# dawa_v2_1.net
KiCad netlist of a schematic drawn in EAGLE
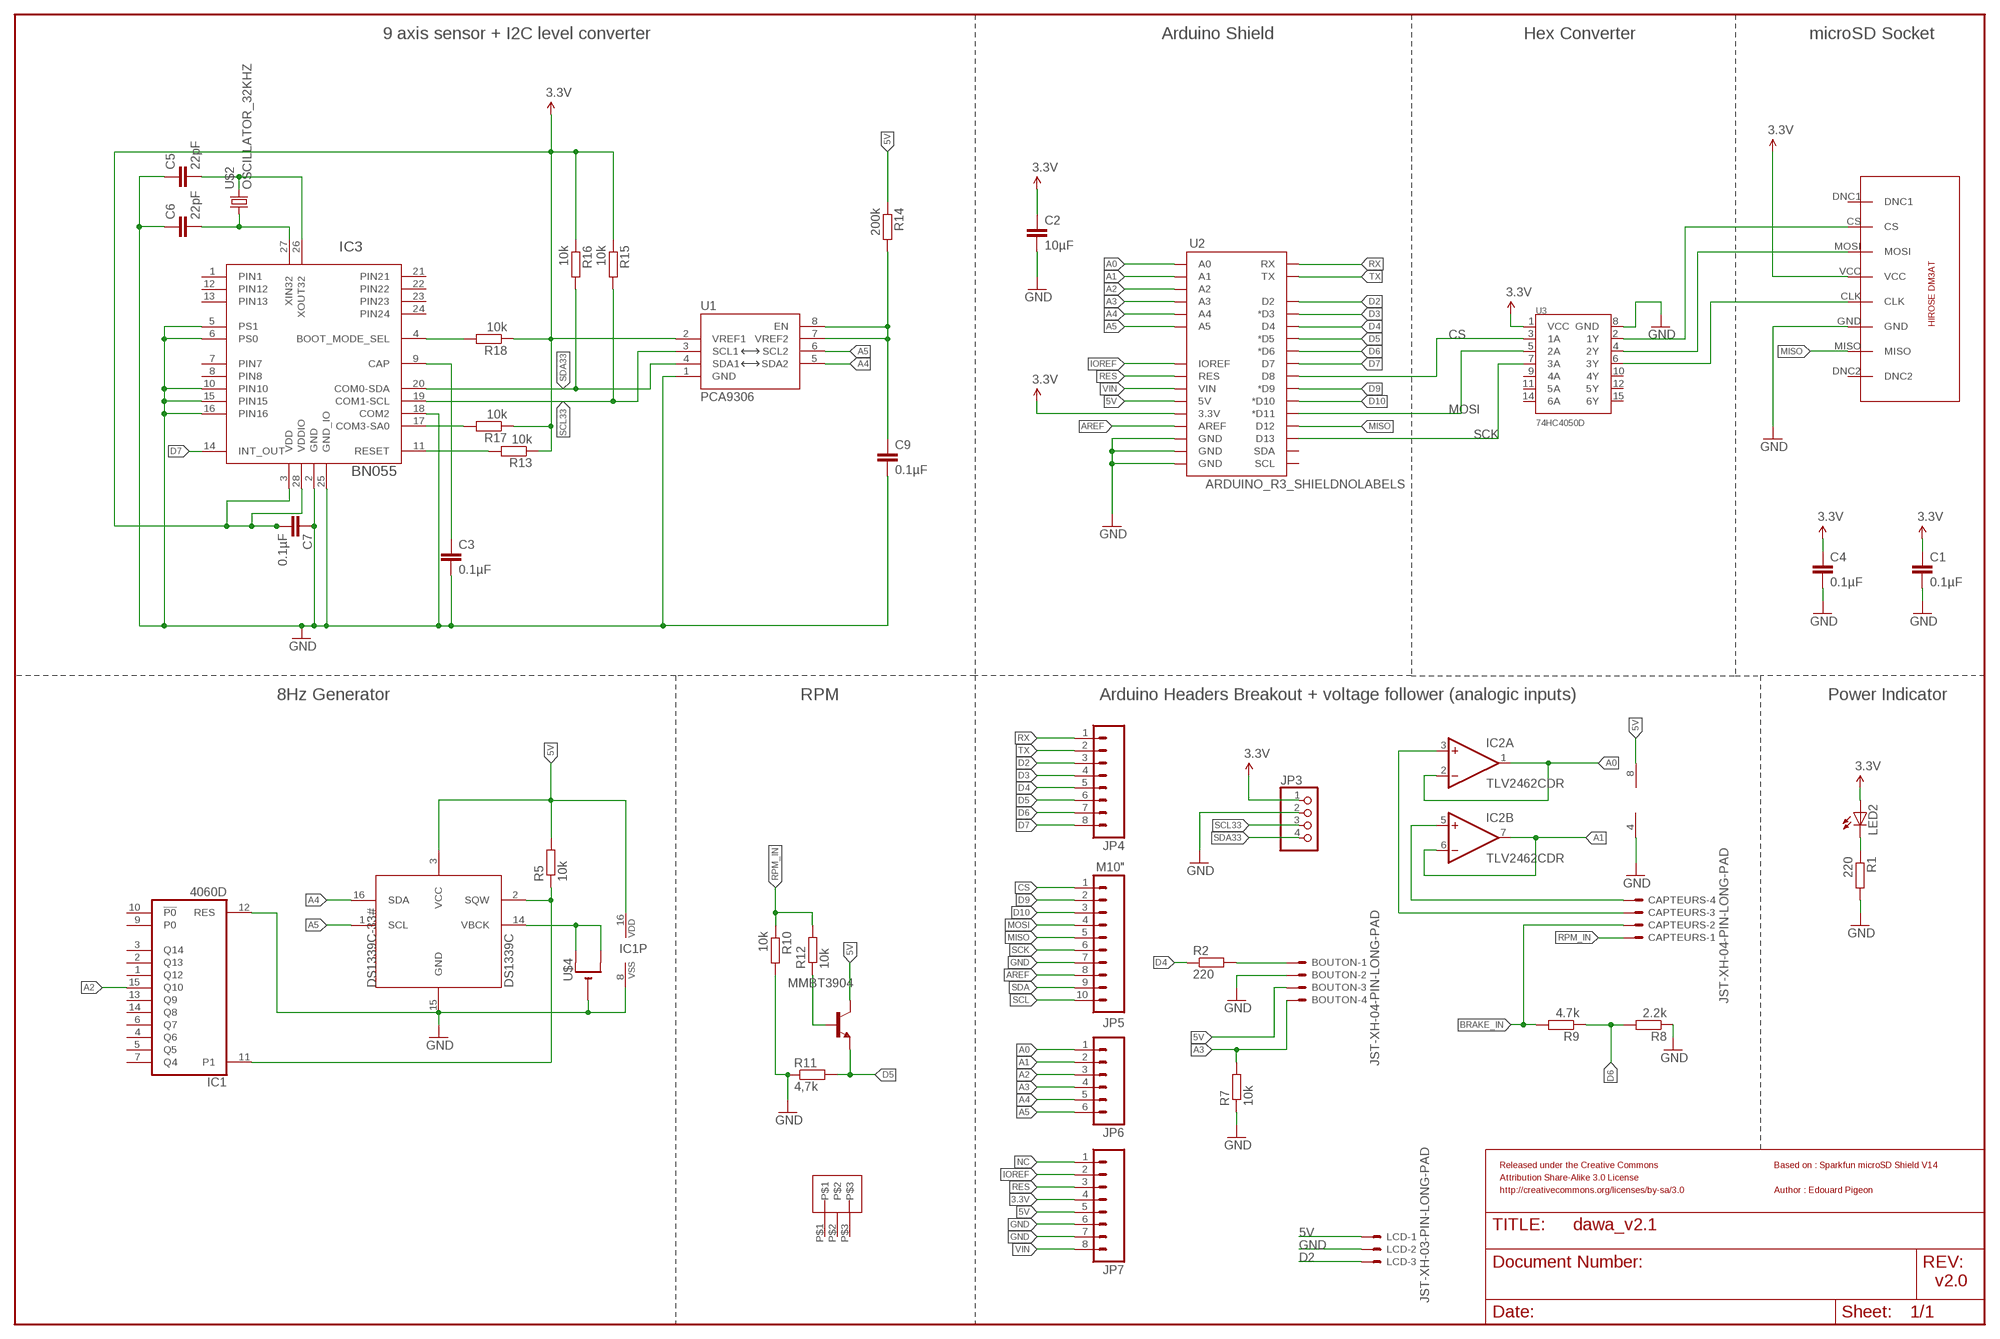
[diagram p0: schematic, sheet 1]

(export (version "E")
  (design (tool "Eeschema 10.0.6"))
  (components
    (comp (ref "BOUTON")
      (value "JST-XH-04-PIN-LONG-PAD")
      (footprint "eagle-import:JST-XH-04-PACKAGE-LONG-PAD")
      (libsource (lib "eagle-import") (part "JST-XH-04-PIN-LONG-PAD"))
    )
    (comp (ref "C1")
      (value "0.1µF")
      (footprint "eagle-import:C1206")
      (libsource (lib "eagle-import") (part "C-EUC1206"))
    )
    (comp (ref "C2")
      (value "10µF")
      (footprint "eagle-import:C1206")
      (libsource (lib "eagle-import") (part "C-EUC1206"))
    )
    (comp (ref "C3")
      (value "0.1µF")
      (footprint "eagle-import:C1206")
      (libsource (lib "eagle-import") (part "C-EUC1206"))
    )
    (comp (ref "C4")
      (value "0.1µF")
      (footprint "eagle-import:C1206")
      (libsource (lib "eagle-import") (part "C-EUC1206"))
    )
    (comp (ref "C5")
      (value "22pF")
      (footprint "eagle-import:C1206")
      (libsource (lib "eagle-import") (part "C-EUC1206"))
    )
    (comp (ref "C6")
      (value "22pF")
      (footprint "eagle-import:C1206")
      (libsource (lib "eagle-import") (part "C-EUC1206"))
    )
    (comp (ref "C7")
      (value "0.1µF")
      (footprint "eagle-import:C1206")
      (libsource (lib "eagle-import") (part "C-EUC1206"))
    )
    (comp (ref "C9")
      (value "0.1µF")
      (footprint "eagle-import:C1206")
      (libsource (lib "eagle-import") (part "C-EUC1206"))
    )
    (comp (ref "CAPTEURS")
      (value "JST-XH-04-PIN-LONG-PAD")
      (footprint "eagle-import:JST-XH-04-PACKAGE-LONG-PAD")
      (libsource (lib "eagle-import") (part "JST-XH-04-PIN-LONG-PAD"))
    )
    (comp (ref "DS1339C-33#")
      (value "DS1339C")
      (footprint "eagle-import:DS1339C")
      (libsource (lib "eagle-import") (part "DS1339C"))
    )
    (comp (ref "IC1")
      (value "4060D")
      (footprint "eagle-import:SO16")
      (libsource (lib "eagle-import") (part "4060D"))
    )
    (comp (ref "IC2")
      (value "TLV2462CDR")
      (footprint "eagle-import:SO08")
      (libsource (lib "eagle-import") (part "LM358MX"))
    )
    (comp (ref "IC3")
      (value "BN055")
      (footprint "eagle-import:LGA-28_3.80X5.20_0.5")
      (fields (field (name "PART_NUMBER") "BNO055"))
      (libsource (lib "eagle-import") (part "1658_BNO055"))
    )
    (comp (ref "JP3")
      (value "PINHD-1X4")
      (footprint "eagle-import:1X04")
      (libsource (lib "eagle-import") (part "PINHD-1X4"))
    )
    (comp (ref "JP4")
      (value "M08")
      (footprint "eagle-import:1X08")
      (libsource (lib "eagle-import") (part "M08"))
    )
    (comp (ref "JP5")
      (value "M10\"")
      (footprint "eagle-import:1X10")
      (libsource (lib "eagle-import") (part "M10{dblquote}"))
    )
    (comp (ref "JP6")
      (value "M06SIP")
      (footprint "eagle-import:1X06")
      (libsource (lib "eagle-import") (part "M06SIP"))
    )
    (comp (ref "JP7")
      (value "M081X08")
      (footprint "eagle-import:1X08")
      (libsource (lib "eagle-import") (part "M081X08"))
    )
    (comp (ref "LCD")
      (value "JST-XH-03-PIN-LONG-PAD")
      (footprint "eagle-import:JST-XH-03-PACKAGE-LONG-PAD")
      (libsource (lib "eagle-import") (part "JST-XH-03-PIN-LONG-PAD"))
    )
    (comp (ref "LED2")
      (value "LEDCHIPLED_1206")
      (footprint "eagle-import:CHIPLED_1206")
      (libsource (lib "eagle-import") (part "LEDCHIPLED_1206"))
    )
    (comp (ref "MMBT3904")
      (value "MMBT3904LT1-NPN-SOT23-BEC")
      (footprint "eagle-import:SOT23-BEC")
      (libsource (lib "eagle-import") (part "-NPN-SOT23-BECMMBT3904LT1"))
    )
    (comp (ref "R1")
      (value "220")
      (footprint "eagle-import:M1206")
      (libsource (lib "eagle-import") (part "resistor_R-EU_M1206"))
    )
    (comp (ref "R2")
      (value "220")
      (footprint "eagle-import:M1206")
      (libsource (lib "eagle-import") (part "resistor_R-EU_M1206"))
    )
    (comp (ref "R5")
      (value "10k")
      (footprint "eagle-import:M1206")
      (libsource (lib "eagle-import") (part "R-EU_M1206"))
    )
    (comp (ref "R7")
      (value "10k")
      (footprint "eagle-import:M1206")
      (libsource (lib "eagle-import") (part "resistor_R-EU_M1206"))
    )
    (comp (ref "R8")
      (value "2.2k")
      (footprint "eagle-import:M1206")
      (libsource (lib "eagle-import") (part "resistor_R-EU_M1206"))
    )
    (comp (ref "R9")
      (value "4.7k")
      (footprint "eagle-import:M1206")
      (libsource (lib "eagle-import") (part "resistor_R-EU_M1206"))
    )
    (comp (ref "R10")
      (value "10k")
      (footprint "eagle-import:M1206")
      (libsource (lib "eagle-import") (part "R-EU_M1206"))
    )
    (comp (ref "R11")
      (value "4,7k")
      (footprint "eagle-import:M1206")
      (libsource (lib "eagle-import") (part "R-EU_M1206"))
    )
    (comp (ref "R12")
      (value "10k")
      (footprint "eagle-import:M1206")
      (libsource (lib "eagle-import") (part "R-EU_M1206"))
    )
    (comp (ref "R13")
      (value "10k")
      (footprint "eagle-import:M1206")
      (libsource (lib "eagle-import") (part "R-EU_M1206"))
    )
    (comp (ref "R14")
      (value "200k")
      (footprint "eagle-import:M1206")
      (libsource (lib "eagle-import") (part "R-EU_M1206"))
    )
    (comp (ref "R15")
      (value "10k")
      (footprint "eagle-import:M1206")
      (libsource (lib "eagle-import") (part "R-EU_M1206"))
    )
    (comp (ref "R16")
      (value "10k")
      (footprint "eagle-import:M1206")
      (libsource (lib "eagle-import") (part "R-EU_M1206"))
    )
    (comp (ref "R17")
      (value "10k")
      (footprint "eagle-import:M1206")
      (libsource (lib "eagle-import") (part "R-EU_M1206"))
    )
    (comp (ref "R18")
      (value "10k")
      (footprint "eagle-import:M1206")
      (libsource (lib "eagle-import") (part "R-EU_M1206"))
    )
    (comp (ref "U$2")
      (value "OSCILLATOR_32KHZ")
      (footprint "eagle-import:OSCILLATOR_SMD")
      (libsource (lib "eagle-import") (part "OSCILLATOR_32KHZ"))
    )
    (comp (ref "U$3")
      (value "3_PIN_JST-XH")
      (footprint "eagle-import:3_PIN_JST-XH")
      (libsource (lib "eagle-import") (part "3_PIN_JST-XH"))
    )
    (comp (ref "U$4")
      (value "CR1220SMT")
      (footprint "eagle-import:CR1220-SMD")
      (libsource (lib "eagle-import") (part "CR1220SMT"))
    )
    (comp (ref "U$5")
      (value "DM3AT")
      (footprint "eagle-import:DM3AT")
      (libsource (lib "eagle-import") (part "DM3AT"))
    )
    (comp (ref "U1")
      (value "PCA9306")
      (footprint "eagle-import:PSOP-8")
      (libsource (lib "eagle-import") (part "PCA9306"))
    )
    (comp (ref "U2")
      (value "ARDUINO_R3_SHIELDNOLABELS")
      (footprint "eagle-import:UNO_R3_SHIELD_NOLABELS")
      (libsource (lib "eagle-import") (part "ARDUINO_R3_SHIELDNOLABELS"))
    )
    (comp (ref "U3")
      (value "74HC4050D")
      (footprint "eagle-import:SO016")
      (libsource (lib "eagle-import") (part "HEX_CONVERTER"))
    )
  )
  (nets
    (net (code "1") (name "3.3V") (class "Default")
      (node (ref "C1") (pin "1") (pinfunction "1_1") (pintype "passive"))
      (node (ref "C2") (pin "1") (pinfunction "1_1") (pintype "passive"))
      (node (ref "C4") (pin "1") (pinfunction "1_1") (pintype "passive"))
      (node (ref "C7") (pin "2") (pinfunction "2_2") (pintype "passive"))
      (node (ref "IC3") (pin "28") (pinfunction "VDDIO_28") (pintype "power_in"))
      (node (ref "IC3") (pin "3") (pinfunction "VDD_3") (pintype "power_in"))
      (node (ref "JP3") (pin "1") (pinfunction "1_1") (pintype "passive"))
      (node (ref "JP7") (pin "4") (pinfunction "4_4") (pintype "passive"))
      (node (ref "LED2") (pin "A") (pinfunction "A_A") (pintype "passive"))
      (node (ref "R13") (pin "1") (pinfunction "1_1") (pintype "passive"))
      (node (ref "R15") (pin "1") (pinfunction "1_1") (pintype "passive"))
      (node (ref "R16") (pin "1") (pinfunction "1_1") (pintype "passive"))
      (node (ref "R17") (pin "1") (pinfunction "1_1") (pintype "passive"))
      (node (ref "R18") (pin "1") (pinfunction "1_1") (pintype "passive"))
      (node (ref "U$5") (pin "VCC") (pinfunction "VCC_VCC") (pintype "bidirectional"))
      (node (ref "U1") (pin "2") (pinfunction "VREF1_2") (pintype "bidirectional"))
      (node (ref "U2") (pin "3.3V") (pinfunction "3.3V_3.3V") (pintype "bidirectional"))
      (node (ref "U3") (pin "1") (pinfunction "VCC_1") (pintype "bidirectional"))
    )
    (net (code "2") (name "5V") (class "Default")
      (node (ref "BOUTON") (pin "3") (pinfunction "S_3") (pintype "passive"))
      (node (ref "DS1339C-33#") (pin "3") (pinfunction "VCC_3") (pintype "bidirectional"))
      (node (ref "IC1") (pin "16") (pinfunction "VDD_16") (pintype "power_in"))
      (node (ref "IC2") (pin "8") (pinfunction "V+_8") (pintype "power_in"))
      (node (ref "JP7") (pin "5") (pinfunction "5_5") (pintype "passive"))
      (node (ref "LCD") (pin "1") (pinfunction "S_1") (pintype "passive"))
      (node (ref "MMBT3904") (pin "C") (pinfunction "C_C") (pintype "passive"))
      (node (ref "R14") (pin "1") (pinfunction "1_1") (pintype "passive"))
      (node (ref "R5") (pin "2") (pinfunction "2_2") (pintype "passive"))
      (node (ref "U2") (pin "5V") (pinfunction "5V_5V") (pintype "bidirectional"))
    )
    (net (code "3") (name "A0") (class "Default")
      (node (ref "IC2") (pin "1") (pinfunction "OUT_1") (pintype "output"))
      (node (ref "IC2") (pin "2") (pinfunction "-IN_2") (pintype "input"))
      (node (ref "JP6") (pin "1") (pinfunction "1_1") (pintype "passive"))
      (node (ref "U2") (pin "A0") (pinfunction "A0_A0") (pintype "bidirectional"))
    )
    (net (code "4") (name "A1") (class "Default")
      (node (ref "IC2") (pin "6") (pinfunction "-IN_6") (pintype "input"))
      (node (ref "IC2") (pin "7") (pinfunction "OUT_7") (pintype "output"))
      (node (ref "JP6") (pin "2") (pinfunction "2_2") (pintype "passive"))
      (node (ref "U2") (pin "A1") (pinfunction "A1_A1") (pintype "bidirectional"))
    )
    (net (code "5") (name "A2") (class "Default")
      (node (ref "IC1") (pin "15") (pinfunction "Q10_15") (pintype "output"))
      (node (ref "JP6") (pin "3") (pinfunction "3_3") (pintype "passive"))
      (node (ref "U2") (pin "A2") (pinfunction "A2_A2") (pintype "bidirectional"))
    )
    (net (code "6") (name "A3") (class "Default")
      (node (ref "BOUTON") (pin "4") (pinfunction "S_4") (pintype "passive"))
      (node (ref "JP6") (pin "4") (pinfunction "4_4") (pintype "passive"))
      (node (ref "R7") (pin "2") (pinfunction "2_2") (pintype "passive"))
      (node (ref "U2") (pin "A3") (pinfunction "A3_A3") (pintype "bidirectional"))
    )
    (net (code "7") (name "A4") (class "Default")
      (node (ref "DS1339C-33#") (pin "16") (pinfunction "SDA_16") (pintype "bidirectional"))
      (node (ref "JP6") (pin "5") (pinfunction "5_5") (pintype "passive"))
      (node (ref "U1") (pin "5") (pinfunction "SDA2_5") (pintype "bidirectional"))
      (node (ref "U2") (pin "A4") (pinfunction "A4_A4") (pintype "bidirectional"))
    )
    (net (code "8") (name "A5") (class "Default")
      (node (ref "DS1339C-33#") (pin "1") (pinfunction "SCL_1") (pintype "bidirectional"))
      (node (ref "JP6") (pin "6") (pinfunction "6_6") (pintype "passive"))
      (node (ref "U1") (pin "6") (pinfunction "SCL2_6") (pintype "bidirectional"))
      (node (ref "U2") (pin "A5") (pinfunction "A5_A5") (pintype "bidirectional"))
    )
    (net (code "9") (name "AREF") (class "Default")
      (node (ref "JP5") (pin "8") (pinfunction "8_8") (pintype "passive"))
      (node (ref "U2") (pin "AREF") (pinfunction "AREF_AREF") (pintype "bidirectional"))
    )
    (net (code "10") (name "BRAKE_IN") (class "Default")
      (node (ref "CAPTEURS") (pin "2") (pinfunction "S_2") (pintype "passive"))
      (node (ref "R9") (pin "2") (pinfunction "2_2") (pintype "passive"))
    )
    (net (code "11") (name "CS") (class "Default")
      (node (ref "JP5") (pin "1") (pinfunction "1_1") (pintype "passive"))
      (node (ref "U2") (pin "D8") (pinfunction "D8_D8") (pintype "bidirectional"))
      (node (ref "U3") (pin "3") (pinfunction "1A_3") (pintype "bidirectional"))
    )
    (net (code "12") (name "D2") (class "Default")
      (node (ref "JP4") (pin "3") (pinfunction "3_3") (pintype "passive"))
      (node (ref "LCD") (pin "3") (pinfunction "S_3") (pintype "passive"))
      (node (ref "U2") (pin "D2") (pinfunction "D2_D2") (pintype "bidirectional"))
    )
    (net (code "13") (name "D3") (class "Default")
      (node (ref "JP4") (pin "4") (pinfunction "4_4") (pintype "passive"))
      (node (ref "U2") (pin "D3") (pinfunction "*D3_D3") (pintype "bidirectional"))
    )
    (net (code "14") (name "D4") (class "Default")
      (node (ref "JP4") (pin "5") (pinfunction "5_5") (pintype "passive"))
      (node (ref "R2") (pin "1") (pinfunction "1_1") (pintype "passive"))
      (node (ref "U2") (pin "D4") (pinfunction "D4_D4") (pintype "bidirectional"))
    )
    (net (code "15") (name "D5") (class "Default")
      (node (ref "JP4") (pin "6") (pinfunction "6_6") (pintype "passive"))
      (node (ref "MMBT3904") (pin "E") (pinfunction "E_E") (pintype "passive"))
      (node (ref "R11") (pin "2") (pinfunction "2_2") (pintype "passive"))
      (node (ref "U2") (pin "D5") (pinfunction "*D5_D5") (pintype "bidirectional"))
    )
    (net (code "16") (name "D6") (class "Default")
      (node (ref "JP4") (pin "7") (pinfunction "7_7") (pintype "passive"))
      (node (ref "R8") (pin "2") (pinfunction "2_2") (pintype "passive"))
      (node (ref "R9") (pin "1") (pinfunction "1_1") (pintype "passive"))
      (node (ref "U2") (pin "D6") (pinfunction "*D6_D6") (pintype "bidirectional"))
    )
    (net (code "17") (name "D7") (class "Default")
      (node (ref "IC3") (pin "14") (pinfunction "INT_OUT_14") (pintype "output"))
      (node (ref "JP4") (pin "8") (pinfunction "8_8") (pintype "passive"))
      (node (ref "U2") (pin "D7") (pinfunction "D7_D7") (pintype "bidirectional"))
    )
    (net (code "18") (name "D9") (class "Default")
      (node (ref "JP5") (pin "2") (pinfunction "2_2") (pintype "passive"))
      (node (ref "U2") (pin "D9") (pinfunction "*D9_D9") (pintype "bidirectional"))
    )
    (net (code "19") (name "D10") (class "Default")
      (node (ref "JP5") (pin "3") (pinfunction "3_3") (pintype "passive"))
      (node (ref "U2") (pin "D10") (pinfunction "*D10_D10") (pintype "bidirectional"))
    )
    (net (code "20") (name "GND") (class "Default")
      (node (ref "BOUTON") (pin "2") (pinfunction "S_2") (pintype "passive"))
      (node (ref "C1") (pin "2") (pinfunction "2_2") (pintype "passive"))
      (node (ref "C2") (pin "2") (pinfunction "2_2") (pintype "passive"))
      (node (ref "C3") (pin "2") (pinfunction "2_2") (pintype "passive"))
      (node (ref "C4") (pin "2") (pinfunction "2_2") (pintype "passive"))
      (node (ref "C5") (pin "1") (pinfunction "1_1") (pintype "passive"))
      (node (ref "C6") (pin "1") (pinfunction "1_1") (pintype "passive"))
      (node (ref "C7") (pin "1") (pinfunction "1_1") (pintype "passive"))
      (node (ref "C9") (pin "2") (pinfunction "2_2") (pintype "passive"))
      (node (ref "DS1339C-33#") (pin "15") (pinfunction "GND_15") (pintype "bidirectional"))
      (node (ref "IC1") (pin "12") (pinfunction "RES_12") (pintype "input"))
      (node (ref "IC1") (pin "8") (pinfunction "VSS_8") (pintype "power_in"))
      (node (ref "IC2") (pin "4") (pinfunction "V-_4") (pintype "power_in"))
      (node (ref "IC3") (pin "10") (pinfunction "PIN10_10") (pintype "passive"))
      (node (ref "IC3") (pin "15") (pinfunction "PIN15_15") (pintype "passive"))
      (node (ref "IC3") (pin "16") (pinfunction "PIN16_16") (pintype "passive"))
      (node (ref "IC3") (pin "18") (pinfunction "COM2_18") (pintype "bidirectional"))
      (node (ref "IC3") (pin "2") (pinfunction "GND_2") (pintype "power_in"))
      (node (ref "IC3") (pin "25") (pinfunction "GND_IO_25") (pintype "power_in"))
      (node (ref "IC3") (pin "5") (pinfunction "PS1_5") (pintype "input"))
      (node (ref "IC3") (pin "6") (pinfunction "PS0_6") (pintype "input"))
      (node (ref "JP3") (pin "2") (pinfunction "2_2") (pintype "passive"))
      (node (ref "JP5") (pin "7") (pinfunction "7_7") (pintype "passive"))
      (node (ref "JP7") (pin "6") (pinfunction "6_6") (pintype "passive"))
      (node (ref "JP7") (pin "7") (pinfunction "7_7") (pintype "passive"))
      (node (ref "LCD") (pin "2") (pinfunction "S_2") (pintype "passive"))
      (node (ref "R1") (pin "2") (pinfunction "2_2") (pintype "passive"))
      (node (ref "R10") (pin "2") (pinfunction "2_2") (pintype "passive"))
      (node (ref "R11") (pin "1") (pinfunction "1_1") (pintype "passive"))
      (node (ref "R7") (pin "1") (pinfunction "1_1") (pintype "passive"))
      (node (ref "R8") (pin "1") (pinfunction "1_1") (pintype "passive"))
      (node (ref "U$4") (pin "-") (pinfunction "-_-") (pintype "passive"))
      (node (ref "U$5") (pin "GND") (pinfunction "GND_GND") (pintype "bidirectional"))
      (node (ref "U1") (pin "1") (pinfunction "GND_1") (pintype "bidirectional"))
      (node (ref "U2") (pin "GND@0") (pinfunction "GND_GND@0") (pintype "bidirectional"))
      (node (ref "U2") (pin "GND@1") (pinfunction "GND_GND@1") (pintype "bidirectional"))
      (node (ref "U2") (pin "GND@2") (pinfunction "GND_GND@2") (pintype "bidirectional"))
      (node (ref "U3") (pin "8") (pinfunction "GND_8") (pintype "bidirectional"))
    )
    (net (code "21") (name "IOREF") (class "Default")
      (node (ref "JP7") (pin "2") (pinfunction "2_2") (pintype "passive"))
      (node (ref "U2") (pin "IOREF") (pinfunction "IOREF_IOREF") (pintype "bidirectional"))
    )
    (net (code "22") (name "MISO") (class "Default")
      (node (ref "JP5") (pin "5") (pinfunction "5_5") (pintype "passive"))
      (node (ref "U$5") (pin "MISO") (pinfunction "MISO_MISO") (pintype "bidirectional"))
      (node (ref "U2") (pin "D12") (pinfunction "D12_D12") (pintype "bidirectional"))
    )
    (net (code "23") (name "MOSI") (class "Default")
      (node (ref "JP5") (pin "4") (pinfunction "4_4") (pintype "passive"))
      (node (ref "U2") (pin "D11") (pinfunction "*D11_D11") (pintype "bidirectional"))
      (node (ref "U3") (pin "5") (pinfunction "2A_5") (pintype "bidirectional"))
    )
    (net (code "24") (name "NC") (class "Default")
      (node (ref "JP7") (pin "1") (pinfunction "1_1") (pintype "passive"))
    )
    (net (code "25") (name "Net-(BOUTONA-S)") (class "Default")
      (node (ref "BOUTON") (pin "1") (pinfunction "S_1") (pintype "passive"))
      (node (ref "R2") (pin "2") (pinfunction "2_2") (pintype "passive"))
    )
    (net (code "26") (name "Net-(CAPTEURSC-S)") (class "Default")
      (node (ref "CAPTEURS") (pin "3") (pinfunction "S_3") (pintype "passive"))
      (node (ref "IC2") (pin "3") (pinfunction "+IN_3") (pintype "input"))
    )
    (net (code "27") (name "Net-(CAPTEURSD-S)") (class "Default")
      (node (ref "CAPTEURS") (pin "4") (pinfunction "S_4") (pintype "passive"))
      (node (ref "IC2") (pin "5") (pinfunction "+IN_5") (pintype "input"))
    )
    (net (code "28") (name "Net-(DS1339C-33#-SQW)") (class "Default")
      (node (ref "DS1339C-33#") (pin "2") (pinfunction "SQW_2") (pintype "bidirectional"))
      (node (ref "IC1") (pin "11") (pinfunction "P1_11") (pintype "input"))
      (node (ref "R5") (pin "1") (pinfunction "1_1") (pintype "passive"))
    )
    (net (code "29") (name "Net-(DS1339C-33#-VBCK)") (class "Default")
      (node (ref "DS1339C-33#") (pin "14") (pinfunction "VBCK_14") (pintype "bidirectional"))
      (node (ref "U$4") (pin "+$1") (pinfunction "+_+$1") (pintype "passive"))
      (node (ref "U$4") (pin "+$2") (pinfunction "+1_+$2") (pintype "passive"))
    )
    (net (code "30") (name "Net-(IC3-BOOT_MODE_SEL)") (class "Default")
      (node (ref "IC3") (pin "4") (pinfunction "BOOT_MODE_SEL_4") (pintype "input"))
      (node (ref "R18") (pin "2") (pinfunction "2_2") (pintype "passive"))
    )
    (net (code "31") (name "Net-(IC3-CAP)") (class "Default")
      (node (ref "C3") (pin "1") (pinfunction "1_1") (pintype "passive"))
      (node (ref "IC3") (pin "9") (pinfunction "CAP_9") (pintype "tri_state"))
    )
    (net (code "32") (name "Net-(IC3-COM3-SA0)") (class "Default")
      (node (ref "IC3") (pin "17") (pinfunction "COM3-SA0_17") (pintype "bidirectional"))
      (node (ref "R17") (pin "2") (pinfunction "2_2") (pintype "passive"))
    )
    (net (code "33") (name "Net-(IC3-RESET)") (class "Default")
      (node (ref "IC3") (pin "11") (pinfunction "RESET_11") (pintype "input"))
      (node (ref "R13") (pin "2") (pinfunction "2_2") (pintype "passive"))
    )
    (net (code "34") (name "Net-(IC3-XIN32)") (class "Default")
      (node (ref "C6") (pin "2") (pinfunction "2_2") (pintype "passive"))
      (node (ref "IC3") (pin "27") (pinfunction "XIN32_27") (pintype "bidirectional"))
      (node (ref "U$2") (pin "1") (pinfunction "1_1") (pintype "passive"))
    )
    (net (code "35") (name "Net-(IC3-XOUT32)") (class "Default")
      (node (ref "C5") (pin "2") (pinfunction "2_2") (pintype "passive"))
      (node (ref "IC3") (pin "26") (pinfunction "XOUT32_26") (pintype "output"))
      (node (ref "U$2") (pin "2") (pinfunction "2_2") (pintype "passive"))
    )
    (net (code "36") (name "Net-(LED2-PadC)") (class "Default")
      (node (ref "LED2") (pin "C") (pinfunction "C_C") (pintype "passive"))
      (node (ref "R1") (pin "1") (pinfunction "1_1") (pintype "passive"))
    )
    (net (code "37") (name "Net-(MMBT3904-PadB)") (class "Default")
      (node (ref "MMBT3904") (pin "B") (pinfunction "B_B") (pintype "passive"))
      (node (ref "R12") (pin "1") (pinfunction "1_1") (pintype "passive"))
    )
    (net (code "38") (name "Net-(U1-EN)") (class "Default")
      (node (ref "C9") (pin "1") (pinfunction "1_1") (pintype "passive"))
      (node (ref "R14") (pin "2") (pinfunction "2_2") (pintype "passive"))
      (node (ref "U1") (pin "7") (pinfunction "VREF2_7") (pintype "bidirectional"))
      (node (ref "U1") (pin "8") (pinfunction "EN_8") (pintype "bidirectional"))
    )
    (net (code "39") (name "Net-(U3-1Y)") (class "Default")
      (node (ref "U$5") (pin "CS") (pinfunction "CS_CS") (pintype "bidirectional"))
      (node (ref "U3") (pin "2") (pinfunction "1Y_2") (pintype "bidirectional"))
    )
    (net (code "40") (name "Net-(U3-2Y)") (class "Default")
      (node (ref "U$5") (pin "MOSI") (pinfunction "MOSI_MOSI") (pintype "bidirectional"))
      (node (ref "U3") (pin "4") (pinfunction "2Y_4") (pintype "bidirectional"))
    )
    (net (code "41") (name "Net-(U3-3Y)") (class "Default")
      (node (ref "U$5") (pin "CLK") (pinfunction "CLK_CLK") (pintype "bidirectional"))
      (node (ref "U3") (pin "6") (pinfunction "3Y_6") (pintype "bidirectional"))
    )
    (net (code "42") (name "RES") (class "Default")
      (node (ref "JP7") (pin "3") (pinfunction "3_3") (pintype "passive"))
      (node (ref "U2") (pin "RES") (pinfunction "RES_RES") (pintype "bidirectional"))
    )
    (net (code "43") (name "RPM_IN") (class "Default")
      (node (ref "CAPTEURS") (pin "1") (pinfunction "S_1") (pintype "passive"))
      (node (ref "R10") (pin "1") (pinfunction "1_1") (pintype "passive"))
      (node (ref "R12") (pin "2") (pinfunction "2_2") (pintype "passive"))
    )
    (net (code "44") (name "RX") (class "Default")
      (node (ref "JP4") (pin "1") (pinfunction "1_1") (pintype "passive"))
      (node (ref "U2") (pin "RX") (pinfunction "RX_RX") (pintype "bidirectional"))
    )
    (net (code "45") (name "SCK") (class "Default")
      (node (ref "JP5") (pin "6") (pinfunction "6_6") (pintype "passive"))
      (node (ref "U2") (pin "D13") (pinfunction "D13_D13") (pintype "bidirectional"))
      (node (ref "U3") (pin "7") (pinfunction "3A_7") (pintype "bidirectional"))
    )
    (net (code "46") (name "SCL") (class "Default")
      (node (ref "JP5") (pin "10") (pinfunction "10_10") (pintype "passive"))
    )
    (net (code "47") (name "SCL33") (class "Default")
      (node (ref "IC3") (pin "19") (pinfunction "COM1-SCL_19") (pintype "bidirectional"))
      (node (ref "JP3") (pin "3") (pinfunction "3_3") (pintype "passive"))
      (node (ref "R15") (pin "2") (pinfunction "2_2") (pintype "passive"))
      (node (ref "U1") (pin "3") (pinfunction "SCL1_3") (pintype "bidirectional"))
    )
    (net (code "48") (name "SDA") (class "Default")
      (node (ref "JP5") (pin "9") (pinfunction "9_9") (pintype "passive"))
    )
    (net (code "49") (name "SDA33") (class "Default")
      (node (ref "IC3") (pin "20") (pinfunction "COM0-SDA_20") (pintype "bidirectional"))
      (node (ref "JP3") (pin "4") (pinfunction "4_4") (pintype "passive"))
      (node (ref "R16") (pin "2") (pinfunction "2_2") (pintype "passive"))
      (node (ref "U1") (pin "4") (pinfunction "SDA1_4") (pintype "bidirectional"))
    )
    (net (code "50") (name "TX") (class "Default")
      (node (ref "JP4") (pin "2") (pinfunction "2_2") (pintype "passive"))
      (node (ref "U2") (pin "TX") (pinfunction "TX_TX") (pintype "bidirectional"))
    )
    (net (code "51") (name "VIN") (class "Default")
      (node (ref "JP7") (pin "8") (pinfunction "8_8") (pintype "passive"))
      (node (ref "U2") (pin "VIN") (pinfunction "VIN_VIN") (pintype "bidirectional"))
    )
    (net (code "52") (name "unconnected-(IC1A-P0-Pad9)") (class "Default")
      (node (ref "IC1") (pin "9") (pinfunction "P0_9") (pintype "output"))
    )
    (net (code "53") (name "unconnected-(IC1A-Q4-Pad7)") (class "Default")
      (node (ref "IC1") (pin "7") (pinfunction "Q4_7") (pintype "output"))
    )
    (net (code "54") (name "unconnected-(IC1A-Q5-Pad5)") (class "Default")
      (node (ref "IC1") (pin "5") (pinfunction "Q5_5") (pintype "output"))
    )
    (net (code "55") (name "unconnected-(IC1A-Q6-Pad4)") (class "Default")
      (node (ref "IC1") (pin "4") (pinfunction "Q6_4") (pintype "output"))
    )
    (net (code "56") (name "unconnected-(IC1A-Q7-Pad6)") (class "Default")
      (node (ref "IC1") (pin "6") (pinfunction "Q7_6") (pintype "output"))
    )
    (net (code "57") (name "unconnected-(IC1A-Q8-Pad14)") (class "Default")
      (node (ref "IC1") (pin "14") (pinfunction "Q8_14") (pintype "output"))
    )
    (net (code "58") (name "unconnected-(IC1A-Q9-Pad13)") (class "Default")
      (node (ref "IC1") (pin "13") (pinfunction "Q9_13") (pintype "output"))
    )
    (net (code "59") (name "unconnected-(IC1A-Q12-Pad1)") (class "Default")
      (node (ref "IC1") (pin "1") (pinfunction "Q12_1") (pintype "output"))
    )
    (net (code "60") (name "unconnected-(IC1A-Q13-Pad2)") (class "Default")
      (node (ref "IC1") (pin "2") (pinfunction "Q13_2") (pintype "output"))
    )
    (net (code "61") (name "unconnected-(IC1A-Q14-Pad3)") (class "Default")
      (node (ref "IC1") (pin "3") (pinfunction "Q14_3") (pintype "output"))
    )
    (net (code "62") (name "unconnected-(IC1A-~{P0}-Pad10)") (class "Default")
      (node (ref "IC1") (pin "10") (pinfunction "~{P0}_10") (pintype "output"))
    )
    (net (code "63") (name "unconnected-(IC3-PIN1-Pad1)") (class "Default")
      (node (ref "IC3") (pin "1") (pinfunction "PIN1_1") (pintype "no_connect"))
    )
    (net (code "64") (name "unconnected-(IC3-PIN7-Pad7)") (class "Default")
      (node (ref "IC3") (pin "7") (pinfunction "PIN7_7") (pintype "tri_state"))
    )
    (net (code "65") (name "unconnected-(IC3-PIN8-Pad8)") (class "Default")
      (node (ref "IC3") (pin "8") (pinfunction "PIN8_8") (pintype "tri_state"))
    )
    (net (code "66") (name "unconnected-(IC3-PIN12-Pad12)") (class "Default")
      (node (ref "IC3") (pin "12") (pinfunction "PIN12_12") (pintype "passive"))
    )
    (net (code "67") (name "unconnected-(IC3-PIN13-Pad13)") (class "Default")
      (node (ref "IC3") (pin "13") (pinfunction "PIN13_13") (pintype "passive"))
    )
    (net (code "68") (name "unconnected-(IC3-PIN21-Pad21)") (class "Default")
      (node (ref "IC3") (pin "21") (pinfunction "PIN21_21") (pintype "passive"))
    )
    (net (code "69") (name "unconnected-(IC3-PIN22-Pad22)") (class "Default")
      (node (ref "IC3") (pin "22") (pinfunction "PIN22_22") (pintype "passive"))
    )
    (net (code "70") (name "unconnected-(IC3-PIN23-Pad23)") (class "Default")
      (node (ref "IC3") (pin "23") (pinfunction "PIN23_23") (pintype "passive"))
    )
    (net (code "71") (name "unconnected-(IC3-PIN24-Pad24)") (class "Default")
      (node (ref "IC3") (pin "24") (pinfunction "PIN24_24") (pintype "passive"))
    )
    (net (code "72") (name "unconnected-(U$3-PadP$1)") (class "Default")
      (node (ref "U$3") (pin "P$1") (pinfunction "P$1_P$1") (pintype "bidirectional"))
    )
    (net (code "73") (name "unconnected-(U$3-PadP$2)") (class "Default")
      (node (ref "U$3") (pin "P$2") (pinfunction "P$2_P$2") (pintype "bidirectional"))
    )
    (net (code "74") (name "unconnected-(U$3-PadP$3)") (class "Default")
      (node (ref "U$3") (pin "P$3") (pinfunction "P$3_P$3") (pintype "bidirectional"))
    )
    (net (code "75") (name "unconnected-(U$5-PadDNC1)") (class "Default")
      (node (ref "U$5") (pin "DNC1") (pinfunction "DNC1_DNC1") (pintype "bidirectional"))
    )
    (net (code "76") (name "unconnected-(U$5-PadDNC2)") (class "Default")
      (node (ref "U$5") (pin "DNC2") (pinfunction "DNC2_DNC2") (pintype "bidirectional"))
    )
    (net (code "77") (name "unconnected-(U2-PadSCL)") (class "Default")
      (node (ref "U2") (pin "SCL") (pinfunction "SCL_SCL") (pintype "bidirectional"))
    )
    (net (code "78") (name "unconnected-(U2-PadSDA)") (class "Default")
      (node (ref "U2") (pin "SDA") (pinfunction "SDA_SDA") (pintype "bidirectional"))
    )
    (net (code "79") (name "unconnected-(U3-4A-Pad9)") (class "Default")
      (node (ref "U3") (pin "9") (pinfunction "4A_9") (pintype "bidirectional"))
    )
    (net (code "80") (name "unconnected-(U3-4Y-Pad10)") (class "Default")
      (node (ref "U3") (pin "10") (pinfunction "4Y_10") (pintype "bidirectional"))
    )
    (net (code "81") (name "unconnected-(U3-5A-Pad11)") (class "Default")
      (node (ref "U3") (pin "11") (pinfunction "5A_11") (pintype "bidirectional"))
    )
    (net (code "82") (name "unconnected-(U3-5Y-Pad12)") (class "Default")
      (node (ref "U3") (pin "12") (pinfunction "5Y_12") (pintype "bidirectional"))
    )
    (net (code "83") (name "unconnected-(U3-6A-Pad14)") (class "Default")
      (node (ref "U3") (pin "14") (pinfunction "6A_14") (pintype "bidirectional"))
    )
    (net (code "84") (name "unconnected-(U3-6Y-Pad15)") (class "Default")
      (node (ref "U3") (pin "15") (pinfunction "6Y_15") (pintype "bidirectional"))
    )
  )
)
